# 6packRev4A.net
KiCad netlist of a schematic drawn in EAGLE
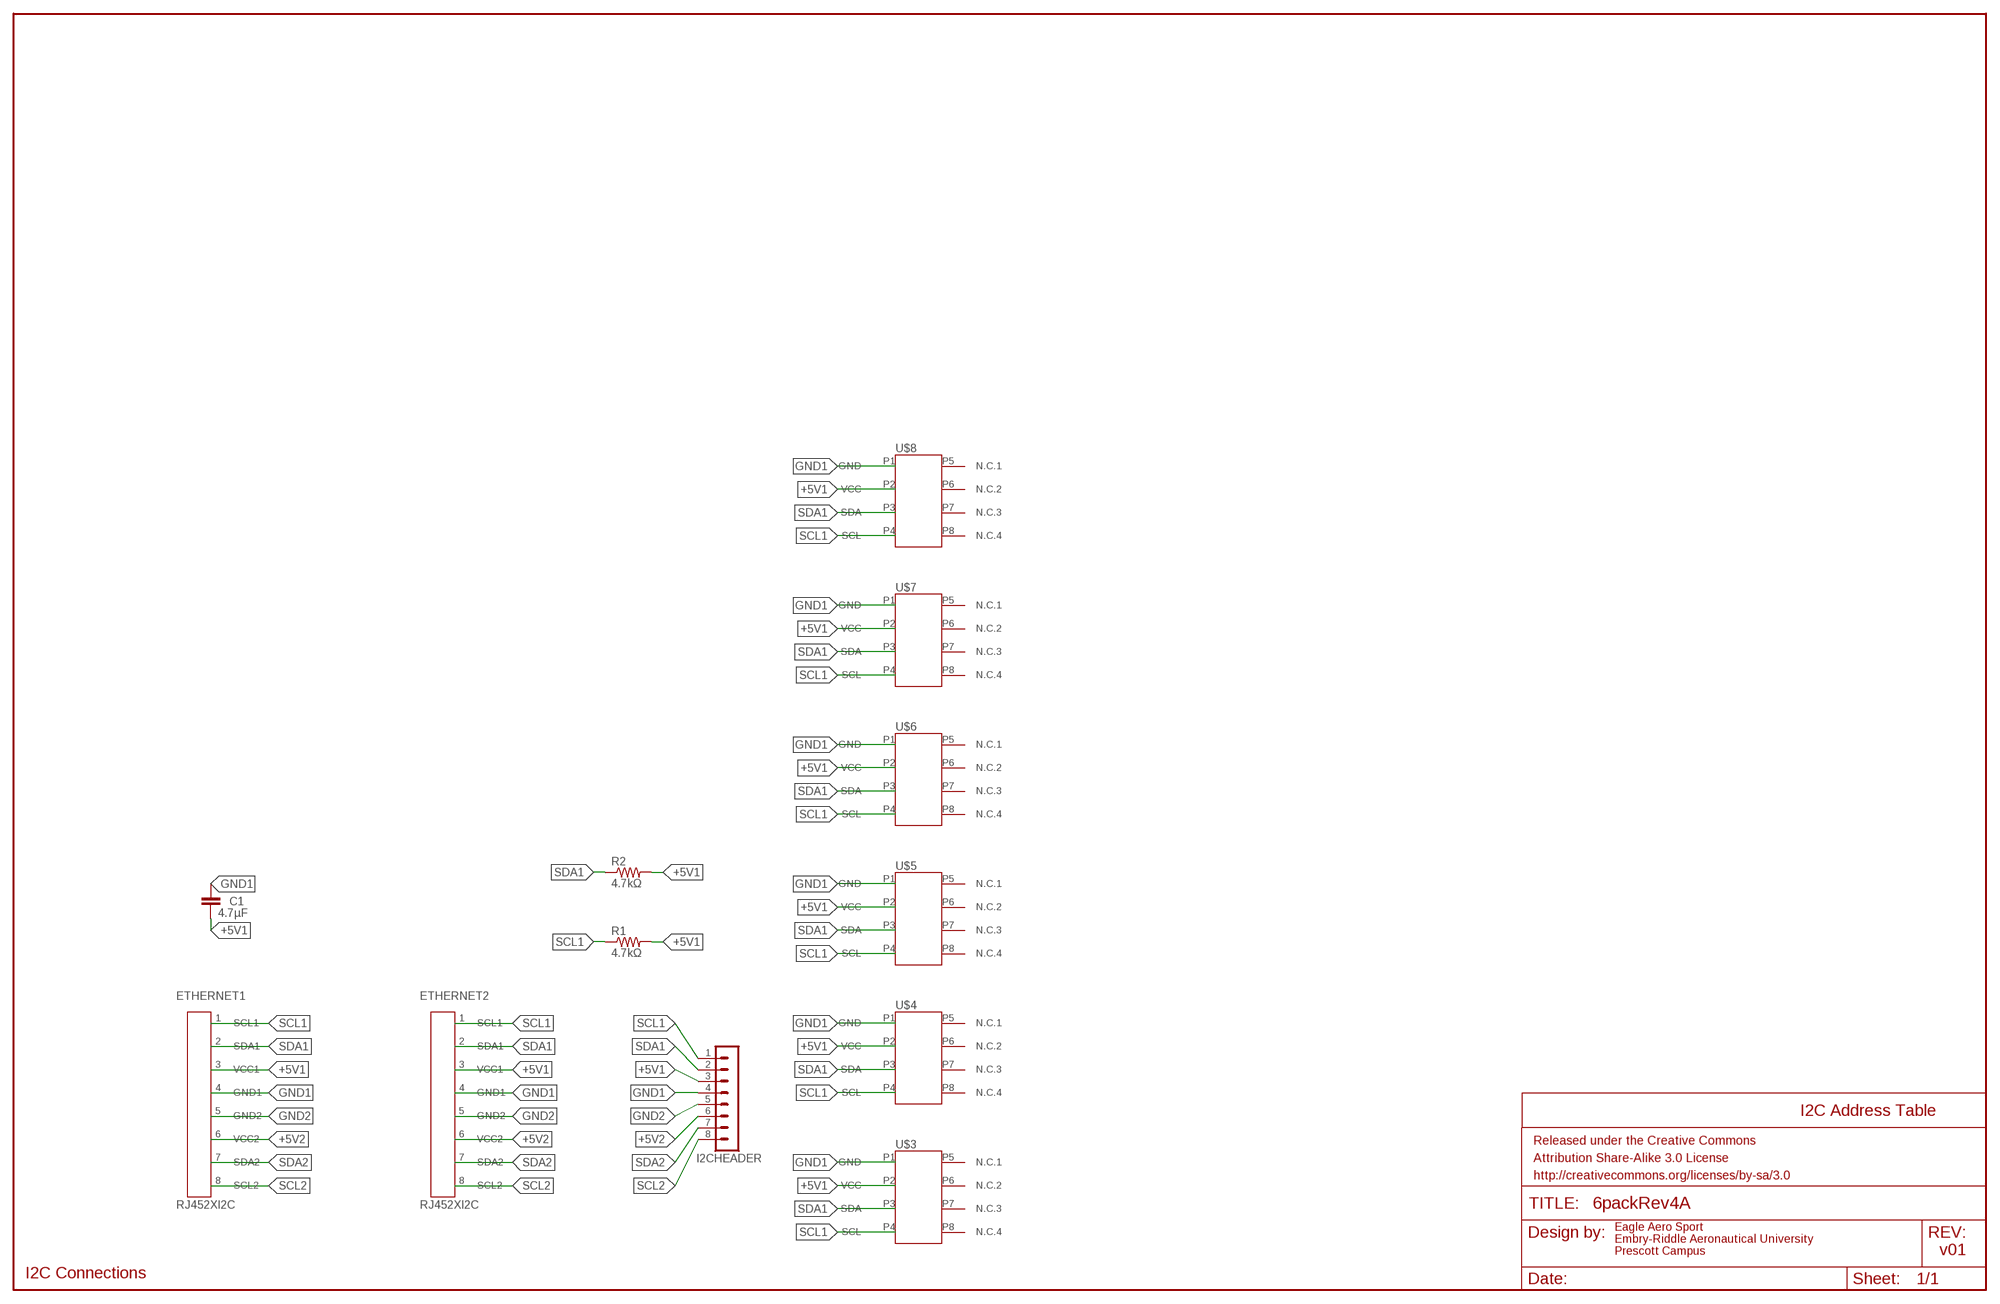
[diagram p0: schematic, sheet 1]

(export (version "E")
  (design (tool "Eeschema 10.0.6"))
  (components
    (comp (ref "C1")
      (value "4.7µF")
      (footprint "eagle-import:CAP-PTH-10MM")
      (libsource (lib "eagle-import") (part "10NF-PTH-10MM-10000V-1-%"))
    )
    (comp (ref "ETHERNET1")
      (value "RJ452XI2C")
      (footprint "eagle-import:RJ45-8")
      (libsource (lib "eagle-import") (part "RJ452XI2C"))
    )
    (comp (ref "ETHERNET2")
      (value "RJ452XI2C")
      (footprint "eagle-import:RJ45-8")
      (libsource (lib "eagle-import") (part "RJ452XI2C"))
    )
    (comp (ref "FRAME1")
      (value "FRAME-LEDGER")
      (footprint "eagle-import:CREATIVE_COMMONS")
      (libsource (lib "eagle-import") (part "FRAME-LEDGER"))
    )
    (comp (ref "I2CHEADER")
      (value "MA08-1")
      (footprint "eagle-import:MA08-1")
      (libsource (lib "eagle-import") (part "MA08-1"))
    )
    (comp (ref "R1")
      (value "4.7kΩ")
      (footprint "eagle-import:0207_12")
      (libsource (lib "eagle-import") (part "R-US_0207/12"))
    )
    (comp (ref "R2")
      (value "4.7kΩ")
      (footprint "eagle-import:0207_12")
      (libsource (lib "eagle-import") (part "R-US_0207/12"))
    )
    (comp (ref "U$3")
      (value "AMS5915")
      (footprint "eagle-import:DIP8W")
      (libsource (lib "eagle-import") (part "AMS5915"))
    )
    (comp (ref "U$4")
      (value "AMS5915")
      (footprint "eagle-import:DIP8W")
      (libsource (lib "eagle-import") (part "AMS5915"))
    )
    (comp (ref "U$5")
      (value "AMS5915")
      (footprint "eagle-import:DIP8W")
      (libsource (lib "eagle-import") (part "AMS5915"))
    )
    (comp (ref "U$6")
      (value "AMS5915")
      (footprint "eagle-import:DIP8W")
      (libsource (lib "eagle-import") (part "AMS5915"))
    )
    (comp (ref "U$7")
      (value "AMS5915")
      (footprint "eagle-import:DIP8W")
      (libsource (lib "eagle-import") (part "AMS5915"))
    )
    (comp (ref "U$8")
      (value "AMS5915")
      (footprint "eagle-import:DIP8W")
      (libsource (lib "eagle-import") (part "AMS5915"))
    )
  )
  (nets
    (net (code "1") (name "+5V1") (class "Default")
      (node (ref "C1") (pin "2") (pinfunction "2_2") (pintype "passive"))
      (node (ref "ETHERNET1") (pin "3") (pinfunction "VCC1_3") (pintype "bidirectional"))
      (node (ref "ETHERNET2") (pin "3") (pinfunction "VCC1_3") (pintype "bidirectional"))
      (node (ref "I2CHEADER") (pin "3") (pinfunction "3_3") (pintype "passive"))
      (node (ref "R1") (pin "2") (pinfunction "2_2") (pintype "passive"))
      (node (ref "R2") (pin "2") (pinfunction "2_2") (pintype "passive"))
      (node (ref "U$3") (pin "P2") (pinfunction "VCC_P2") (pintype "power_in"))
      (node (ref "U$4") (pin "P2") (pinfunction "VCC_P2") (pintype "power_in"))
      (node (ref "U$5") (pin "P2") (pinfunction "VCC_P2") (pintype "power_in"))
      (node (ref "U$6") (pin "P2") (pinfunction "VCC_P2") (pintype "power_in"))
      (node (ref "U$7") (pin "P2") (pinfunction "VCC_P2") (pintype "power_in"))
      (node (ref "U$8") (pin "P2") (pinfunction "VCC_P2") (pintype "power_in"))
    )
    (net (code "2") (name "+5V2") (class "Default")
      (node (ref "ETHERNET1") (pin "6") (pinfunction "VCC2_6") (pintype "bidirectional"))
      (node (ref "ETHERNET2") (pin "6") (pinfunction "VCC2_6") (pintype "bidirectional"))
      (node (ref "I2CHEADER") (pin "6") (pinfunction "6_6") (pintype "passive"))
    )
    (net (code "3") (name "GND1") (class "Default")
      (node (ref "C1") (pin "1") (pinfunction "1_1") (pintype "passive"))
      (node (ref "ETHERNET1") (pin "4") (pinfunction "GND1_4") (pintype "bidirectional"))
      (node (ref "ETHERNET2") (pin "4") (pinfunction "GND1_4") (pintype "bidirectional"))
      (node (ref "I2CHEADER") (pin "4") (pinfunction "4_4") (pintype "passive"))
      (node (ref "U$3") (pin "P1") (pinfunction "GND_P1") (pintype "bidirectional"))
      (node (ref "U$4") (pin "P1") (pinfunction "GND_P1") (pintype "bidirectional"))
      (node (ref "U$5") (pin "P1") (pinfunction "GND_P1") (pintype "bidirectional"))
      (node (ref "U$6") (pin "P1") (pinfunction "GND_P1") (pintype "bidirectional"))
      (node (ref "U$7") (pin "P1") (pinfunction "GND_P1") (pintype "bidirectional"))
      (node (ref "U$8") (pin "P1") (pinfunction "GND_P1") (pintype "bidirectional"))
    )
    (net (code "4") (name "GND2") (class "Default")
      (node (ref "ETHERNET1") (pin "5") (pinfunction "GND2_5") (pintype "bidirectional"))
      (node (ref "ETHERNET2") (pin "5") (pinfunction "GND2_5") (pintype "bidirectional"))
      (node (ref "I2CHEADER") (pin "5") (pinfunction "5_5") (pintype "passive"))
    )
    (net (code "5") (name "SCL1") (class "Default")
      (node (ref "ETHERNET1") (pin "1") (pinfunction "SCL1_1") (pintype "bidirectional"))
      (node (ref "ETHERNET2") (pin "1") (pinfunction "SCL1_1") (pintype "bidirectional"))
      (node (ref "I2CHEADER") (pin "1") (pinfunction "1_1") (pintype "passive"))
      (node (ref "R1") (pin "1") (pinfunction "1_1") (pintype "passive"))
      (node (ref "U$3") (pin "P4") (pinfunction "SCL_P4") (pintype "bidirectional"))
      (node (ref "U$4") (pin "P4") (pinfunction "SCL_P4") (pintype "bidirectional"))
      (node (ref "U$5") (pin "P4") (pinfunction "SCL_P4") (pintype "bidirectional"))
      (node (ref "U$6") (pin "P4") (pinfunction "SCL_P4") (pintype "bidirectional"))
      (node (ref "U$7") (pin "P4") (pinfunction "SCL_P4") (pintype "bidirectional"))
      (node (ref "U$8") (pin "P4") (pinfunction "SCL_P4") (pintype "bidirectional"))
    )
    (net (code "6") (name "SCL2") (class "Default")
      (node (ref "ETHERNET1") (pin "8") (pinfunction "SCL2_8") (pintype "bidirectional"))
      (node (ref "ETHERNET2") (pin "8") (pinfunction "SCL2_8") (pintype "bidirectional"))
      (node (ref "I2CHEADER") (pin "8") (pinfunction "8_8") (pintype "passive"))
    )
    (net (code "7") (name "SDA1") (class "Default")
      (node (ref "ETHERNET1") (pin "2") (pinfunction "SDA1_2") (pintype "bidirectional"))
      (node (ref "ETHERNET2") (pin "2") (pinfunction "SDA1_2") (pintype "bidirectional"))
      (node (ref "I2CHEADER") (pin "2") (pinfunction "2_2") (pintype "passive"))
      (node (ref "R2") (pin "1") (pinfunction "1_1") (pintype "passive"))
      (node (ref "U$3") (pin "P3") (pinfunction "SDA_P3") (pintype "bidirectional"))
      (node (ref "U$4") (pin "P3") (pinfunction "SDA_P3") (pintype "bidirectional"))
      (node (ref "U$5") (pin "P3") (pinfunction "SDA_P3") (pintype "bidirectional"))
      (node (ref "U$6") (pin "P3") (pinfunction "SDA_P3") (pintype "bidirectional"))
      (node (ref "U$7") (pin "P3") (pinfunction "SDA_P3") (pintype "bidirectional"))
      (node (ref "U$8") (pin "P3") (pinfunction "SDA_P3") (pintype "bidirectional"))
    )
    (net (code "8") (name "SDA2") (class "Default")
      (node (ref "ETHERNET1") (pin "7") (pinfunction "SDA2_7") (pintype "bidirectional"))
      (node (ref "ETHERNET2") (pin "7") (pinfunction "SDA2_7") (pintype "bidirectional"))
      (node (ref "I2CHEADER") (pin "7") (pinfunction "7_7") (pintype "passive"))
    )
    (net (code "9") (name "unconnected-(U$3-N.C.1-PadP5)") (class "Default")
      (node (ref "U$3") (pin "P5") (pinfunction "N.C.1_P5") (pintype "no_connect"))
    )
    (net (code "10") (name "unconnected-(U$3-N.C.2-PadP6)") (class "Default")
      (node (ref "U$3") (pin "P6") (pinfunction "N.C.2_P6") (pintype "no_connect"))
    )
    (net (code "11") (name "unconnected-(U$3-N.C.3-PadP7)") (class "Default")
      (node (ref "U$3") (pin "P7") (pinfunction "N.C.3_P7") (pintype "no_connect"))
    )
    (net (code "12") (name "unconnected-(U$3-N.C.4-PadP8)") (class "Default")
      (node (ref "U$3") (pin "P8") (pinfunction "N.C.4_P8") (pintype "no_connect"))
    )
    (net (code "13") (name "unconnected-(U$4-N.C.1-PadP5)") (class "Default")
      (node (ref "U$4") (pin "P5") (pinfunction "N.C.1_P5") (pintype "no_connect"))
    )
    (net (code "14") (name "unconnected-(U$4-N.C.2-PadP6)") (class "Default")
      (node (ref "U$4") (pin "P6") (pinfunction "N.C.2_P6") (pintype "no_connect"))
    )
    (net (code "15") (name "unconnected-(U$4-N.C.3-PadP7)") (class "Default")
      (node (ref "U$4") (pin "P7") (pinfunction "N.C.3_P7") (pintype "no_connect"))
    )
    (net (code "16") (name "unconnected-(U$4-N.C.4-PadP8)") (class "Default")
      (node (ref "U$4") (pin "P8") (pinfunction "N.C.4_P8") (pintype "no_connect"))
    )
    (net (code "17") (name "unconnected-(U$5-N.C.1-PadP5)") (class "Default")
      (node (ref "U$5") (pin "P5") (pinfunction "N.C.1_P5") (pintype "no_connect"))
    )
    (net (code "18") (name "unconnected-(U$5-N.C.2-PadP6)") (class "Default")
      (node (ref "U$5") (pin "P6") (pinfunction "N.C.2_P6") (pintype "no_connect"))
    )
    (net (code "19") (name "unconnected-(U$5-N.C.3-PadP7)") (class "Default")
      (node (ref "U$5") (pin "P7") (pinfunction "N.C.3_P7") (pintype "no_connect"))
    )
    (net (code "20") (name "unconnected-(U$5-N.C.4-PadP8)") (class "Default")
      (node (ref "U$5") (pin "P8") (pinfunction "N.C.4_P8") (pintype "no_connect"))
    )
    (net (code "21") (name "unconnected-(U$6-N.C.1-PadP5)") (class "Default")
      (node (ref "U$6") (pin "P5") (pinfunction "N.C.1_P5") (pintype "no_connect"))
    )
    (net (code "22") (name "unconnected-(U$6-N.C.2-PadP6)") (class "Default")
      (node (ref "U$6") (pin "P6") (pinfunction "N.C.2_P6") (pintype "no_connect"))
    )
    (net (code "23") (name "unconnected-(U$6-N.C.3-PadP7)") (class "Default")
      (node (ref "U$6") (pin "P7") (pinfunction "N.C.3_P7") (pintype "no_connect"))
    )
    (net (code "24") (name "unconnected-(U$6-N.C.4-PadP8)") (class "Default")
      (node (ref "U$6") (pin "P8") (pinfunction "N.C.4_P8") (pintype "no_connect"))
    )
    (net (code "25") (name "unconnected-(U$7-N.C.1-PadP5)") (class "Default")
      (node (ref "U$7") (pin "P5") (pinfunction "N.C.1_P5") (pintype "no_connect"))
    )
    (net (code "26") (name "unconnected-(U$7-N.C.2-PadP6)") (class "Default")
      (node (ref "U$7") (pin "P6") (pinfunction "N.C.2_P6") (pintype "no_connect"))
    )
    (net (code "27") (name "unconnected-(U$7-N.C.3-PadP7)") (class "Default")
      (node (ref "U$7") (pin "P7") (pinfunction "N.C.3_P7") (pintype "no_connect"))
    )
    (net (code "28") (name "unconnected-(U$7-N.C.4-PadP8)") (class "Default")
      (node (ref "U$7") (pin "P8") (pinfunction "N.C.4_P8") (pintype "no_connect"))
    )
    (net (code "29") (name "unconnected-(U$8-N.C.1-PadP5)") (class "Default")
      (node (ref "U$8") (pin "P5") (pinfunction "N.C.1_P5") (pintype "no_connect"))
    )
    (net (code "30") (name "unconnected-(U$8-N.C.2-PadP6)") (class "Default")
      (node (ref "U$8") (pin "P6") (pinfunction "N.C.2_P6") (pintype "no_connect"))
    )
    (net (code "31") (name "unconnected-(U$8-N.C.3-PadP7)") (class "Default")
      (node (ref "U$8") (pin "P7") (pinfunction "N.C.3_P7") (pintype "no_connect"))
    )
    (net (code "32") (name "unconnected-(U$8-N.C.4-PadP8)") (class "Default")
      (node (ref "U$8") (pin "P8") (pinfunction "N.C.4_P8") (pintype "no_connect"))
    )
  )
)
